# Sheet_Gloves.net
KiCad netlist of a schematic drawn in Altium Designer
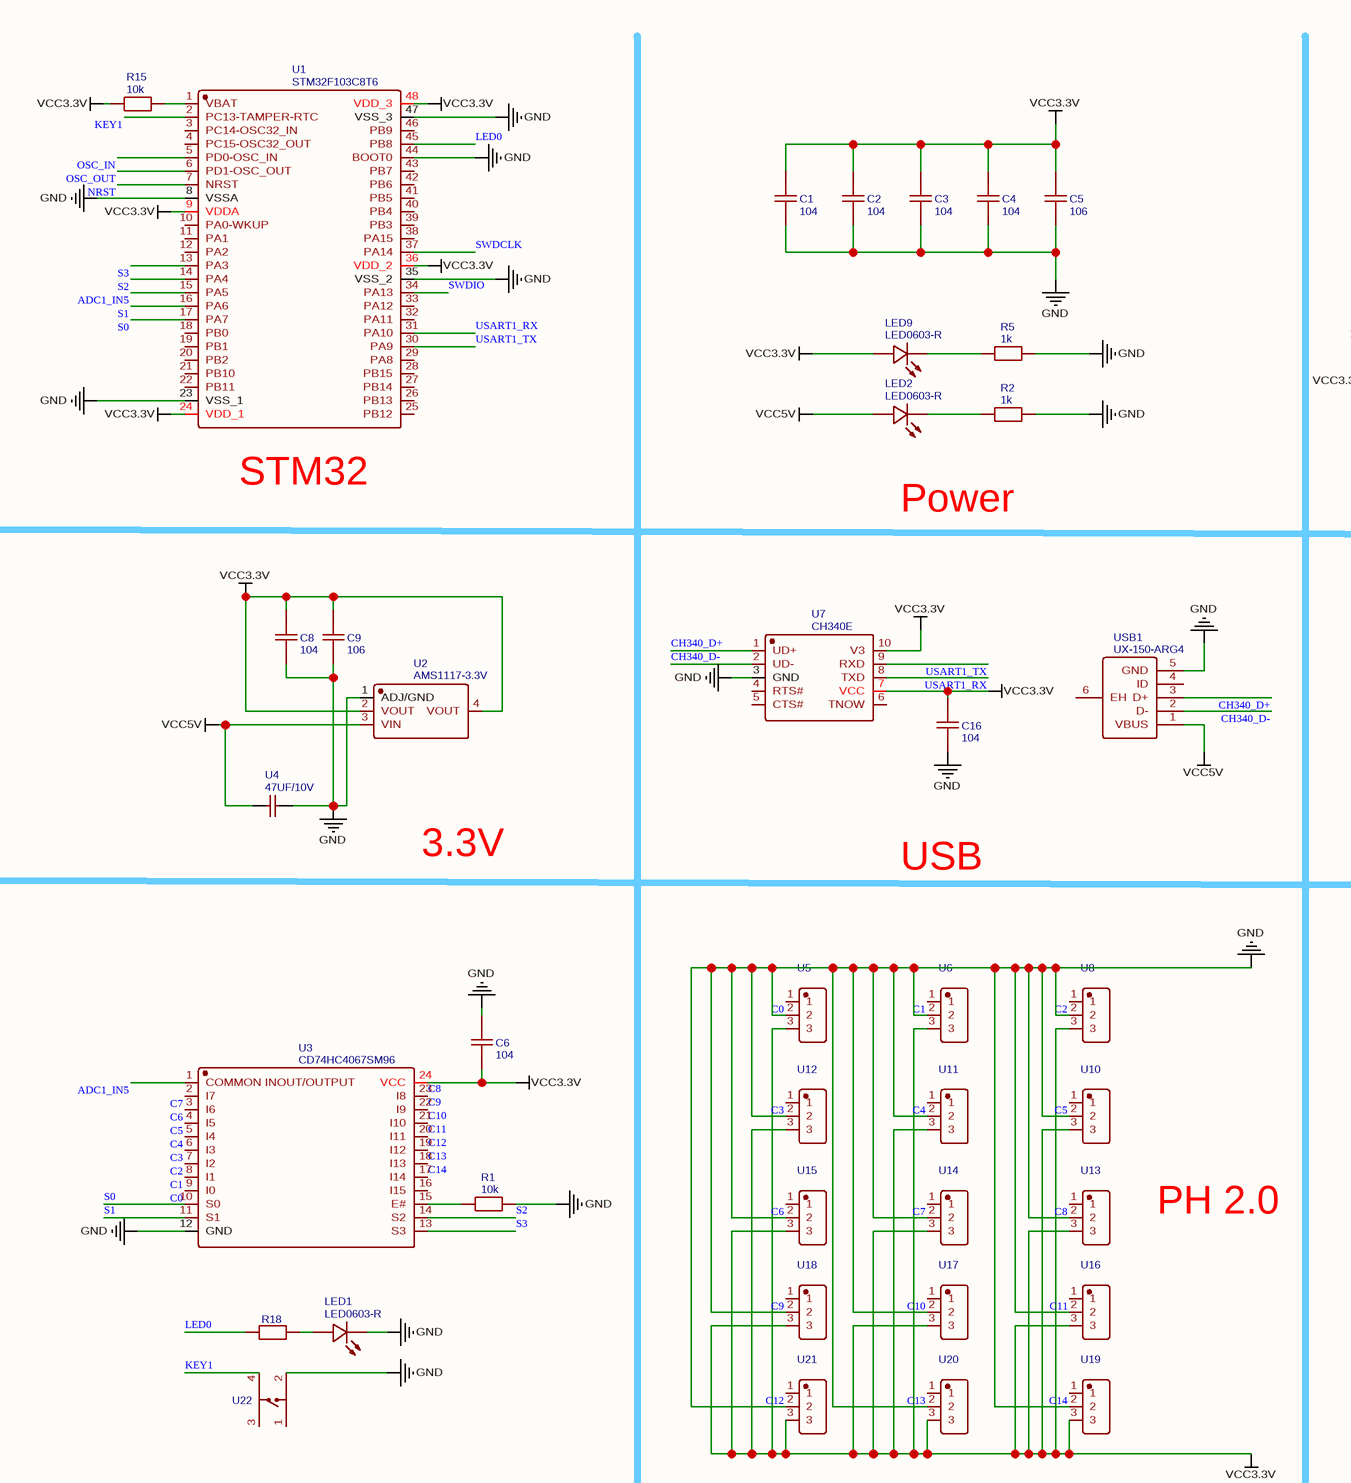
[diagram p0: Sheet_Gloves.schdoc, top left]
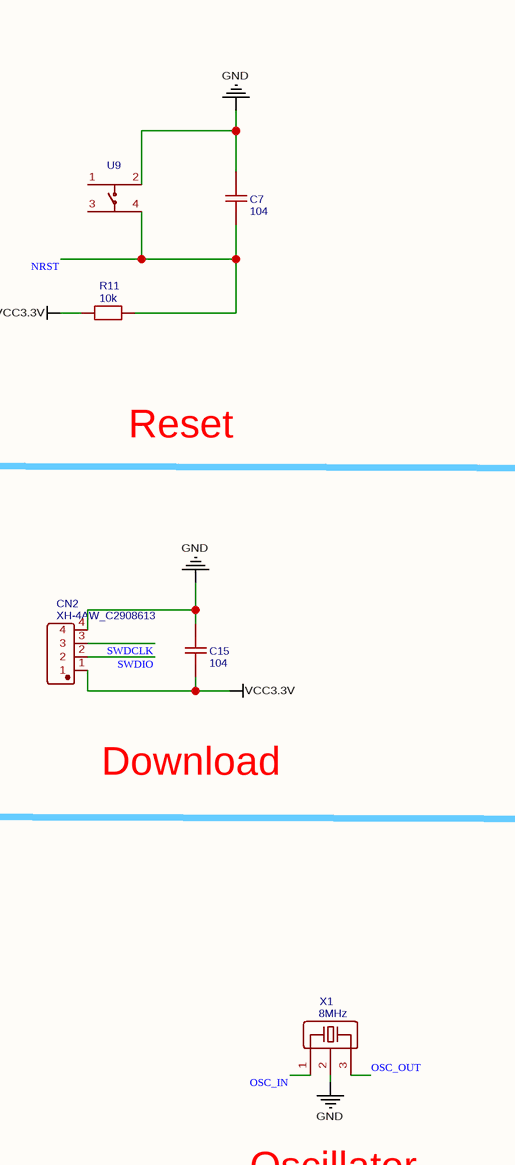
[diagram p1: Sheet_Gloves.schdoc, top right]
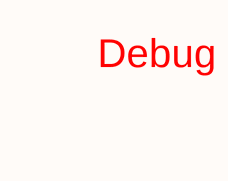
[diagram p2: Sheet_Gloves.schdoc, bottom left]
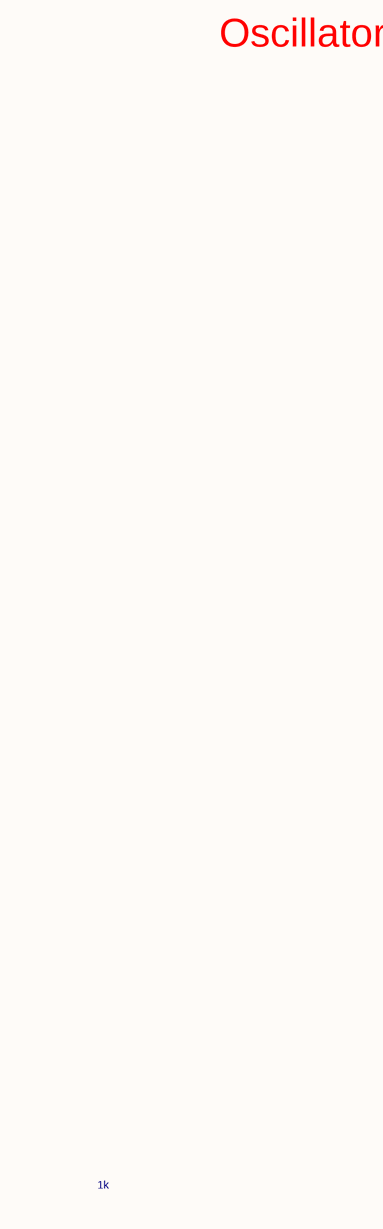
[diagram p3: Sheet_Gloves.schdoc, bottom right]

(export (version "E")
  (design (tool "Eeschema 10.0.6"))
  (components
    (comp (ref "C1")
      (value "104")
      (fields (field (name "CONTRIBUTOR") "LCEDA_Lib"))
      (libsource (lib "altium-import") (part "root_1_104_"))
    )
    (comp (ref "C2")
      (value "104")
      (fields (field (name "CONTRIBUTOR") "LCEDA_Lib"))
      (libsource (lib "altium-import") (part "root_1_104_"))
    )
    (comp (ref "C3")
      (value "104")
      (fields (field (name "CONTRIBUTOR") "LCEDA_Lib"))
      (libsource (lib "altium-import") (part "root_1_104_"))
    )
    (comp (ref "C4")
      (value "104")
      (fields (field (name "CONTRIBUTOR") "LCEDA_Lib"))
      (libsource (lib "altium-import") (part "root_1_104_"))
    )
    (comp (ref "C5")
      (value "106")
      (fields (field (name "CONTRIBUTOR") "LCEDA_Lib"))
      (libsource (lib "altium-import") (part "root_1_106_"))
    )
    (comp (ref "C6")
      (value "104")
      (fields (field (name "CONTRIBUTOR") "LCEDA_Lib"))
      (libsource (lib "altium-import") (part "root_1_104_"))
    )
    (comp (ref "C7")
      (value "104")
      (fields (field (name "CONTRIBUTOR") "LCEDA_Lib"))
      (libsource (lib "altium-import") (part "root_1_104_"))
    )
    (comp (ref "C8")
      (value "104")
      (fields (field (name "CONTRIBUTOR") "LCEDA_Lib"))
      (libsource (lib "altium-import") (part "root_1_104_"))
    )
    (comp (ref "C9")
      (value "106")
      (fields (field (name "CONTRIBUTOR") "LCEDA_Lib"))
      (libsource (lib "altium-import") (part "root_1_106_"))
    )
    (comp (ref "C15")
      (value "104")
      (fields (field (name "CONTRIBUTOR") "LCEDA_Lib"))
      (libsource (lib "altium-import") (part "root_1_104_"))
    )
    (comp (ref "C16")
      (value "104")
      (fields (field (name "CONTRIBUTOR") "LCEDA_Lib"))
      (libsource (lib "altium-import") (part "root_1_104_"))
    )
    (comp (ref "CN2")
      (value "XH-4AW_C2908613")
      (fields
        (field (name "MANUFACTURER") "HCTL(华灿天禄)")
        (field (name "MANUFACTURER PART") "XH-4AW")
        (field (name "CONTRIBUTOR") "LCSC")
      )
      (libsource (lib "altium-import") (part "root_2_XH-4AW_C2908613_"))
    )
    (comp (ref "LED1")
      (value "LED0603-R")
      (fields (field (name "CONTRIBUTOR") "LCSC"))
      (libsource (lib "altium-import") (part "root_2_LED0603-R_"))
    )
    (comp (ref "LED2")
      (value "LED0603-R")
      (fields (field (name "CONTRIBUTOR") "LCSC"))
      (libsource (lib "altium-import") (part "root_2_LED0603-R_"))
    )
    (comp (ref "LED9")
      (value "LED0603-R")
      (fields (field (name "CONTRIBUTOR") "LCSC"))
      (libsource (lib "altium-import") (part "root_2_LED0603-R_"))
    )
    (comp (ref "R1")
      (value "10k")
      (fields (field (name "CONTRIBUTOR") "LCEDA_Lib"))
      (libsource (lib "altium-import") (part "root_0_10k_"))
    )
    (comp (ref "R2")
      (value "1k")
      (fields (field (name "CONTRIBUTOR") "LCEDA_Lib"))
      (libsource (lib "altium-import") (part "root_0_1k_"))
    )
    (comp (ref "R5")
      (value "1k")
      (fields (field (name "CONTRIBUTOR") "LCEDA_Lib"))
      (libsource (lib "altium-import") (part "root_0_1k_"))
    )
    (comp (ref "R11")
      (value "10k")
      (fields (field (name "CONTRIBUTOR") "LCEDA_Lib"))
      (libsource (lib "altium-import") (part "root_0_10k_"))
    )
    (comp (ref "R15")
      (value "10k")
      (fields (field (name "CONTRIBUTOR") "LCEDA_Lib"))
      (libsource (lib "altium-import") (part "root_2_10k_"))
    )
    (comp (ref "R18")
      (value "1k")
      (fields (field (name "CONTRIBUTOR") "LCEDA_Lib"))
      (libsource (lib "altium-import") (part "root_0_1k_"))
    )
    (comp (ref "U1")
      (value "STM32F103C8T6")
      (fields (field (name "MANUFACTURER") "ST(意法半导体)"))
      (libsource (lib "altium-import") (part "root_0_STM32F103C8T6_"))
    )
    (comp (ref "U2")
      (value "AMS1117-3.3V")
      (fields (field (name "MANUFACTURER") "WPMtek(维攀微)") (field (name "CONTRIBUTOR") "LCSC"))
      (libsource (lib "altium-import") (part "root_0_AMS1117-3.3V_"))
    )
    (comp (ref "U3")
      (value "CD74HC4067SM96")
      (fields (field (name "MANUFACTURER") "TI(德州仪器)"))
      (libsource (lib "altium-import") (part "root_0_CD74HC4067SM96_"))
    )
    (comp (ref "U4")
      (value "47UF/10V")
      (fields (field (name "MANUFACTURER PART") "47uF/10V") (field (name "CONTRIBUTOR") "LCSC"))
      (libsource (lib "altium-import") (part "root_0_47UF/10V_"))
    )
    (comp (ref "U5")
      (value "WAFER-PH2.0-3PZZ-R62")
      (fields (field (name "MANUFACTURER") "XUNPU(讯普)") (field (name "CONTRIBUTOR") "lcsc"))
      (libsource (lib "altium-import") (part "root_0_WAFER-PH2.0-3PZZ-R62_"))
    )
    (comp (ref "U6")
      (value "WAFER-PH2.0-3PZZ-R62")
      (fields (field (name "MANUFACTURER") "XUNPU(讯普)") (field (name "CONTRIBUTOR") "lcsc"))
      (libsource (lib "altium-import") (part "root_0_WAFER-PH2.0-3PZZ-R62_"))
    )
    (comp (ref "U7")
      (value "CH340E")
      (fields (field (name "MANUFACTURER") "WCH(南京沁恒)"))
      (libsource (lib "altium-import") (part "root_0_CH340E_"))
    )
    (comp (ref "U8")
      (value "WAFER-PH2.0-3PZZ-R62")
      (fields (field (name "MANUFACTURER") "XUNPU(讯普)") (field (name "CONTRIBUTOR") "lcsc"))
      (libsource (lib "altium-import") (part "root_0_WAFER-PH2.0-3PZZ-R62_"))
    )
    (comp (ref "U9")
      (value "TPS645-5NC60")
      (fields (field (name "MANUFACTURER") "ROCPU Switches(台普)") (field (name "CONTRIBUTOR") "lcsc"))
      (libsource (lib "altium-import") (part "root_0_TPS645-5NC60_"))
    )
    (comp (ref "U10")
      (value "WAFER-PH2.0-3PZZ-R62")
      (fields (field (name "MANUFACTURER") "XUNPU(讯普)") (field (name "CONTRIBUTOR") "lcsc"))
      (libsource (lib "altium-import") (part "root_0_WAFER-PH2.0-3PZZ-R62_"))
    )
    (comp (ref "U11")
      (value "WAFER-PH2.0-3PZZ-R62")
      (fields (field (name "MANUFACTURER") "XUNPU(讯普)") (field (name "CONTRIBUTOR") "lcsc"))
      (libsource (lib "altium-import") (part "root_0_WAFER-PH2.0-3PZZ-R62_"))
    )
    (comp (ref "U12")
      (value "WAFER-PH2.0-3PZZ-R62")
      (fields (field (name "MANUFACTURER") "XUNPU(讯普)") (field (name "CONTRIBUTOR") "lcsc"))
      (libsource (lib "altium-import") (part "root_0_WAFER-PH2.0-3PZZ-R62_"))
    )
    (comp (ref "U13")
      (value "WAFER-PH2.0-3PZZ-R62")
      (fields (field (name "MANUFACTURER") "XUNPU(讯普)") (field (name "CONTRIBUTOR") "lcsc"))
      (libsource (lib "altium-import") (part "root_0_WAFER-PH2.0-3PZZ-R62_"))
    )
    (comp (ref "U14")
      (value "WAFER-PH2.0-3PZZ-R62")
      (fields (field (name "MANUFACTURER") "XUNPU(讯普)") (field (name "CONTRIBUTOR") "lcsc"))
      (libsource (lib "altium-import") (part "root_0_WAFER-PH2.0-3PZZ-R62_"))
    )
    (comp (ref "U15")
      (value "WAFER-PH2.0-3PZZ-R62")
      (fields (field (name "MANUFACTURER") "XUNPU(讯普)") (field (name "CONTRIBUTOR") "lcsc"))
      (libsource (lib "altium-import") (part "root_0_WAFER-PH2.0-3PZZ-R62_"))
    )
    (comp (ref "U16")
      (value "WAFER-PH2.0-3PZZ-R62")
      (fields (field (name "MANUFACTURER") "XUNPU(讯普)") (field (name "CONTRIBUTOR") "lcsc"))
      (libsource (lib "altium-import") (part "root_0_WAFER-PH2.0-3PZZ-R62_"))
    )
    (comp (ref "U17")
      (value "WAFER-PH2.0-3PZZ-R62")
      (fields (field (name "MANUFACTURER") "XUNPU(讯普)") (field (name "CONTRIBUTOR") "lcsc"))
      (libsource (lib "altium-import") (part "root_0_WAFER-PH2.0-3PZZ-R62_"))
    )
    (comp (ref "U18")
      (value "WAFER-PH2.0-3PZZ-R62")
      (fields (field (name "MANUFACTURER") "XUNPU(讯普)") (field (name "CONTRIBUTOR") "lcsc"))
      (libsource (lib "altium-import") (part "root_0_WAFER-PH2.0-3PZZ-R62_"))
    )
    (comp (ref "U19")
      (value "WAFER-PH2.0-3PZZ-R62")
      (fields (field (name "MANUFACTURER") "XUNPU(讯普)") (field (name "CONTRIBUTOR") "lcsc"))
      (libsource (lib "altium-import") (part "root_0_WAFER-PH2.0-3PZZ-R62_"))
    )
    (comp (ref "U20")
      (value "WAFER-PH2.0-3PZZ-R62")
      (fields (field (name "MANUFACTURER") "XUNPU(讯普)") (field (name "CONTRIBUTOR") "lcsc"))
      (libsource (lib "altium-import") (part "root_0_WAFER-PH2.0-3PZZ-R62_"))
    )
    (comp (ref "U21")
      (value "WAFER-PH2.0-3PZZ-R62")
      (fields (field (name "MANUFACTURER") "XUNPU(讯普)") (field (name "CONTRIBUTOR") "lcsc"))
      (libsource (lib "altium-import") (part "root_0_WAFER-PH2.0-3PZZ-R62_"))
    )
    (comp (ref "U22")
      (value "TPS645-5NC60")
      (fields (field (name "MANUFACTURER") "ROCPU Switches(台普)") (field (name "CONTRIBUTOR") "lcsc"))
      (libsource (lib "altium-import") (part "root_1_TPS645-5NC60_"))
    )
    (comp (ref "USB1")
      (value "UX-150-ARG4")
      (fields (field (name "MANUFACTURER") "XUNPU(讯普)") (field (name "CONTRIBUTOR") "LCSC"))
      (libsource (lib "altium-import") (part "root_2_UX-150-ARG4_"))
    )
    (comp (ref "X1")
      (value "8MHz")
      (fields (field (name "MANUFACTURER PART") "CSTCE8M00G52-R0") (field (name "MANUFACTURER") "muRata(村田)"))
      (libsource (lib "altium-import") (part "root_0_8MHz_"))
    )
  )
  (nets
    (net (code "1") (name "/ADC1_IN5") (class "Default")
      (node (ref "U1") (pin "15") (pinfunction "PA5_15") (pintype "passive"))
      (node (ref "U3") (pin "1") (pinfunction "COMMON_INOUT/OUTPUT_1") (pintype "passive"))
    )
    (net (code "2") (name "/C0") (class "Default")
      (node (ref "U3") (pin "9") (pinfunction "I0_9") (pintype "passive"))
      (node (ref "U5") (pin "1") (pinfunction "1_1") (pintype "passive"))
    )
    (net (code "3") (name "/C1") (class "Default")
      (node (ref "U3") (pin "8") (pinfunction "I1_8") (pintype "passive"))
      (node (ref "U6") (pin "1") (pinfunction "1_1") (pintype "passive"))
    )
    (net (code "4") (name "/C2") (class "Default")
      (node (ref "U3") (pin "7") (pinfunction "I2_7") (pintype "passive"))
      (node (ref "U8") (pin "1") (pinfunction "1_1") (pintype "passive"))
    )
    (net (code "5") (name "/C3") (class "Default")
      (node (ref "U12") (pin "1") (pinfunction "1_1") (pintype "passive"))
      (node (ref "U3") (pin "6") (pinfunction "I3_6") (pintype "passive"))
    )
    (net (code "6") (name "/C4") (class "Default")
      (node (ref "U11") (pin "1") (pinfunction "1_1") (pintype "passive"))
      (node (ref "U3") (pin "5") (pinfunction "I4_5") (pintype "passive"))
    )
    (net (code "7") (name "/C5") (class "Default")
      (node (ref "U10") (pin "1") (pinfunction "1_1") (pintype "passive"))
      (node (ref "U3") (pin "4") (pinfunction "I5_4") (pintype "passive"))
    )
    (net (code "8") (name "/C6") (class "Default")
      (node (ref "U15") (pin "1") (pinfunction "1_1") (pintype "passive"))
      (node (ref "U3") (pin "3") (pinfunction "I6_3") (pintype "passive"))
    )
    (net (code "9") (name "/C7") (class "Default")
      (node (ref "U14") (pin "1") (pinfunction "1_1") (pintype "passive"))
      (node (ref "U3") (pin "2") (pinfunction "I7_2") (pintype "passive"))
    )
    (net (code "10") (name "/C8") (class "Default")
      (node (ref "U13") (pin "1") (pinfunction "1_1") (pintype "passive"))
      (node (ref "U3") (pin "23") (pinfunction "I8_23") (pintype "passive"))
    )
    (net (code "11") (name "/C9") (class "Default")
      (node (ref "U18") (pin "1") (pinfunction "1_1") (pintype "passive"))
      (node (ref "U3") (pin "22") (pinfunction "I9_22") (pintype "passive"))
    )
    (net (code "12") (name "/C10") (class "Default")
      (node (ref "U17") (pin "1") (pinfunction "1_1") (pintype "passive"))
      (node (ref "U3") (pin "21") (pinfunction "I10_21") (pintype "passive"))
    )
    (net (code "13") (name "/C11") (class "Default")
      (node (ref "U16") (pin "1") (pinfunction "1_1") (pintype "passive"))
      (node (ref "U3") (pin "20") (pinfunction "I11_20") (pintype "passive"))
    )
    (net (code "14") (name "/C12") (class "Default")
      (node (ref "U21") (pin "1") (pinfunction "1_1") (pintype "passive"))
      (node (ref "U3") (pin "19") (pinfunction "I12_19") (pintype "passive"))
    )
    (net (code "15") (name "/C13") (class "Default")
      (node (ref "U20") (pin "1") (pinfunction "1_1") (pintype "passive"))
      (node (ref "U3") (pin "18") (pinfunction "I13_18") (pintype "passive"))
    )
    (net (code "16") (name "/C14") (class "Default")
      (node (ref "U19") (pin "1") (pinfunction "1_1") (pintype "passive"))
      (node (ref "U3") (pin "17") (pinfunction "I14_17") (pintype "passive"))
    )
    (net (code "17") (name "/CH340_D+") (class "Default")
      (node (ref "U7") (pin "1") (pinfunction "UD+_1") (pintype "passive"))
      (node (ref "USB1") (pin "3") (pinfunction "D+_3") (pintype "passive"))
    )
    (net (code "18") (name "/CH340_D-") (class "Default")
      (node (ref "U7") (pin "2") (pinfunction "UD-_2") (pintype "passive"))
      (node (ref "USB1") (pin "2") (pinfunction "D-_2") (pintype "passive"))
    )
    (net (code "19") (name "/KEY1") (class "Default")
      (node (ref "U1") (pin "2") (pinfunction "PC13-TAMPER-RTC_2") (pintype "passive"))
      (node (ref "U22") (pin "4") (pinfunction "4_4") (pintype "passive"))
    )
    (net (code "20") (name "/LED0") (class "Default")
      (node (ref "R18") (pin "1") (pinfunction "1_1") (pintype "passive"))
      (node (ref "U1") (pin "45") (pinfunction "PB8_45") (pintype "passive"))
    )
    (net (code "21") (name "/NRST") (class "Default")
      (node (ref "C7") (pin "1") (pinfunction "1_1") (pintype "passive"))
      (node (ref "R11") (pin "2") (pinfunction "2_2") (pintype "passive"))
      (node (ref "U1") (pin "7") (pinfunction "NRST_7") (pintype "passive"))
      (node (ref "U9") (pin "4") (pinfunction "4_4") (pintype "passive"))
    )
    (net (code "22") (name "/OSC_IN") (class "Default")
      (node (ref "U1") (pin "5") (pinfunction "PD0-OSC_IN_5") (pintype "passive"))
      (node (ref "X1") (pin "1") (pinfunction "1_1") (pintype "passive"))
    )
    (net (code "23") (name "/OSC_OUT") (class "Default")
      (node (ref "U1") (pin "6") (pinfunction "PD1-OSC_OUT_6") (pintype "passive"))
      (node (ref "X1") (pin "3") (pinfunction "3_3") (pintype "passive"))
    )
    (net (code "24") (name "/S0") (class "Default")
      (node (ref "U1") (pin "17") (pinfunction "PA7_17") (pintype "passive"))
      (node (ref "U3") (pin "10") (pinfunction "S0_10") (pintype "passive"))
    )
    (net (code "25") (name "/S1") (class "Default")
      (node (ref "U1") (pin "16") (pinfunction "PA6_16") (pintype "passive"))
      (node (ref "U3") (pin "11") (pinfunction "S1_11") (pintype "passive"))
    )
    (net (code "26") (name "/S2") (class "Default")
      (node (ref "U1") (pin "14") (pinfunction "PA4_14") (pintype "passive"))
      (node (ref "U3") (pin "14") (pinfunction "S2_14") (pintype "passive"))
    )
    (net (code "27") (name "/S3") (class "Default")
      (node (ref "U1") (pin "13") (pinfunction "PA3_13") (pintype "passive"))
      (node (ref "U3") (pin "13") (pinfunction "S3_13") (pintype "passive"))
    )
    (net (code "28") (name "/SWDCLK") (class "Default")
      (node (ref "CN2") (pin "3") (pinfunction "3_3") (pintype "passive"))
      (node (ref "U1") (pin "37") (pinfunction "PA14_37") (pintype "passive"))
    )
    (net (code "29") (name "/SWDIO") (class "Default")
      (node (ref "CN2") (pin "2") (pinfunction "2_2") (pintype "passive"))
      (node (ref "U1") (pin "34") (pinfunction "PA13_34") (pintype "passive"))
    )
    (net (code "30") (name "/USART1_RX") (class "Default")
      (node (ref "U1") (pin "31") (pinfunction "PA10_31") (pintype "passive"))
      (node (ref "U7") (pin "8") (pinfunction "TXD_8") (pintype "passive"))
    )
    (net (code "31") (name "/USART1_TX") (class "Default")
      (node (ref "U1") (pin "30") (pinfunction "PA9_30") (pintype "passive"))
      (node (ref "U7") (pin "9") (pinfunction "RXD_9") (pintype "passive"))
    )
    (net (code "32") (name "GND") (class "Default")
      (node (ref "C1") (pin "1") (pinfunction "1_1") (pintype "passive"))
      (node (ref "C15") (pin "2") (pinfunction "2_2") (pintype "passive"))
      (node (ref "C16") (pin "1") (pinfunction "1_1") (pintype "passive"))
      (node (ref "C2") (pin "1") (pinfunction "1_1") (pintype "passive"))
      (node (ref "C3") (pin "1") (pinfunction "1_1") (pintype "passive"))
      (node (ref "C4") (pin "1") (pinfunction "1_1") (pintype "passive"))
      (node (ref "C5") (pin "1") (pinfunction "1_1") (pintype "passive"))
      (node (ref "C6") (pin "2") (pinfunction "2_2") (pintype "passive"))
      (node (ref "C7") (pin "2") (pinfunction "2_2") (pintype "passive"))
      (node (ref "C8") (pin "1") (pinfunction "1_1") (pintype "passive"))
      (node (ref "C9") (pin "1") (pinfunction "1_1") (pintype "passive"))
      (node (ref "CN2") (pin "4") (pinfunction "4_4") (pintype "passive"))
      (node (ref "LED1") (pin "2") (pinfunction "K_2") (pintype "passive"))
      (node (ref "R1") (pin "2") (pinfunction "2_2") (pintype "passive"))
      (node (ref "R2") (pin "2") (pinfunction "2_2") (pintype "passive"))
      (node (ref "R5") (pin "2") (pinfunction "2_2") (pintype "passive"))
      (node (ref "U1") (pin "23") (pinfunction "VSS_1_23") (pintype "passive"))
      (node (ref "U1") (pin "35") (pinfunction "VSS_2_35") (pintype "passive"))
      (node (ref "U1") (pin "44") (pinfunction "BOOT0_44") (pintype "passive"))
      (node (ref "U1") (pin "47") (pinfunction "VSS_3_47") (pintype "passive"))
      (node (ref "U1") (pin "8") (pinfunction "VSSA_8") (pintype "passive"))
      (node (ref "U10") (pin "2") (pinfunction "2_2") (pintype "passive"))
      (node (ref "U11") (pin "2") (pinfunction "2_2") (pintype "passive"))
      (node (ref "U12") (pin "2") (pinfunction "2_2") (pintype "passive"))
      (node (ref "U13") (pin "2") (pinfunction "2_2") (pintype "passive"))
      (node (ref "U14") (pin "2") (pinfunction "2_2") (pintype "passive"))
      (node (ref "U15") (pin "2") (pinfunction "2_2") (pintype "passive"))
      (node (ref "U16") (pin "2") (pinfunction "2_2") (pintype "passive"))
      (node (ref "U17") (pin "2") (pinfunction "2_2") (pintype "passive"))
      (node (ref "U18") (pin "2") (pinfunction "2_2") (pintype "passive"))
      (node (ref "U19") (pin "2") (pinfunction "2_2") (pintype "passive"))
      (node (ref "U2") (pin "1") (pinfunction "ADJ/GND_1") (pintype "passive"))
      (node (ref "U20") (pin "2") (pinfunction "2_2") (pintype "passive"))
      (node (ref "U21") (pin "2") (pinfunction "2_2") (pintype "passive"))
      (node (ref "U22") (pin "2") (pinfunction "2_2") (pintype "passive"))
      (node (ref "U3") (pin "12") (pinfunction "GND_12") (pintype "passive"))
      (node (ref "U4") (pin "2") (pinfunction "2_2") (pintype "passive"))
      (node (ref "U5") (pin "2") (pinfunction "2_2") (pintype "passive"))
      (node (ref "U6") (pin "2") (pinfunction "2_2") (pintype "passive"))
      (node (ref "U7") (pin "3") (pinfunction "GND_3") (pintype "passive"))
      (node (ref "U8") (pin "2") (pinfunction "2_2") (pintype "passive"))
      (node (ref "U9") (pin "2") (pinfunction "2_2") (pintype "passive"))
      (node (ref "USB1") (pin "5") (pinfunction "GND_5") (pintype "passive"))
      (node (ref "X1") (pin "2") (pinfunction "2_2") (pintype "passive"))
    )
    (net (code "33") (name "Net-(LED1-A)") (class "Default")
      (node (ref "LED1") (pin "1") (pinfunction "A_1") (pintype "passive"))
      (node (ref "R18") (pin "2") (pinfunction "2_2") (pintype "passive"))
    )
    (net (code "34") (name "Net-(LED2-K)") (class "Default")
      (node (ref "LED2") (pin "2") (pinfunction "K_2") (pintype "passive"))
      (node (ref "R2") (pin "1") (pinfunction "1_1") (pintype "passive"))
    )
    (net (code "35") (name "Net-(LED9-K)") (class "Default")
      (node (ref "LED9") (pin "2") (pinfunction "K_2") (pintype "passive"))
      (node (ref "R5") (pin "1") (pinfunction "1_1") (pintype "passive"))
    )
    (net (code "36") (name "Net-(U1-VBAT)") (class "Default")
      (node (ref "R15") (pin "1") (pinfunction "1_1") (pintype "passive"))
      (node (ref "U1") (pin "1") (pinfunction "VBAT_1") (pintype "passive"))
    )
    (net (code "37") (name "Net-(U3-E#)") (class "Default")
      (node (ref "R1") (pin "1") (pinfunction "1_1") (pintype "passive"))
      (node (ref "U3") (pin "15") (pinfunction "E#_15") (pintype "passive"))
    )
    (net (code "38") (name "VCC3.3V") (class "Default")
      (node (ref "C1") (pin "2") (pinfunction "2_2") (pintype "passive"))
      (node (ref "C15") (pin "1") (pinfunction "1_1") (pintype "passive"))
      (node (ref "C16") (pin "2") (pinfunction "2_2") (pintype "passive"))
      (node (ref "C2") (pin "2") (pinfunction "2_2") (pintype "passive"))
      (node (ref "C3") (pin "2") (pinfunction "2_2") (pintype "passive"))
      (node (ref "C4") (pin "2") (pinfunction "2_2") (pintype "passive"))
      (node (ref "C5") (pin "2") (pinfunction "2_2") (pintype "passive"))
      (node (ref "C6") (pin "1") (pinfunction "1_1") (pintype "passive"))
      (node (ref "C8") (pin "2") (pinfunction "2_2") (pintype "passive"))
      (node (ref "C9") (pin "2") (pinfunction "2_2") (pintype "passive"))
      (node (ref "CN2") (pin "1") (pinfunction "1_1") (pintype "passive"))
      (node (ref "LED9") (pin "1") (pinfunction "A_1") (pintype "passive"))
      (node (ref "R11") (pin "1") (pinfunction "1_1") (pintype "passive"))
      (node (ref "R15") (pin "2") (pinfunction "2_2") (pintype "passive"))
      (node (ref "U1") (pin "24") (pinfunction "VDD_1_24") (pintype "passive"))
      (node (ref "U1") (pin "36") (pinfunction "VDD_2_36") (pintype "passive"))
      (node (ref "U1") (pin "48") (pinfunction "VDD_3_48") (pintype "passive"))
      (node (ref "U1") (pin "9") (pinfunction "VDDA_9") (pintype "passive"))
      (node (ref "U10") (pin "3") (pinfunction "3_3") (pintype "passive"))
      (node (ref "U11") (pin "3") (pinfunction "3_3") (pintype "passive"))
      (node (ref "U12") (pin "3") (pinfunction "3_3") (pintype "passive"))
      (node (ref "U13") (pin "3") (pinfunction "3_3") (pintype "passive"))
      (node (ref "U14") (pin "3") (pinfunction "3_3") (pintype "passive"))
      (node (ref "U15") (pin "3") (pinfunction "3_3") (pintype "passive"))
      (node (ref "U16") (pin "3") (pinfunction "3_3") (pintype "passive"))
      (node (ref "U17") (pin "3") (pinfunction "3_3") (pintype "passive"))
      (node (ref "U18") (pin "3") (pinfunction "3_3") (pintype "passive"))
      (node (ref "U19") (pin "3") (pinfunction "3_3") (pintype "passive"))
      (node (ref "U2") (pin "2") (pinfunction "VOUT_2") (pintype "passive"))
      (node (ref "U2") (pin "4") (pinfunction "VOUT_4") (pintype "passive"))
      (node (ref "U20") (pin "3") (pinfunction "3_3") (pintype "passive"))
      (node (ref "U21") (pin "3") (pinfunction "3_3") (pintype "passive"))
      (node (ref "U3") (pin "24") (pinfunction "VCC_24") (pintype "passive"))
      (node (ref "U5") (pin "3") (pinfunction "3_3") (pintype "passive"))
      (node (ref "U6") (pin "3") (pinfunction "3_3") (pintype "passive"))
      (node (ref "U7") (pin "10") (pinfunction "V3_10") (pintype "passive"))
      (node (ref "U7") (pin "7") (pinfunction "VCC_7") (pintype "passive"))
      (node (ref "U8") (pin "3") (pinfunction "3_3") (pintype "passive"))
    )
    (net (code "39") (name "VCC5V") (class "Default")
      (node (ref "LED2") (pin "1") (pinfunction "A_1") (pintype "passive"))
      (node (ref "U2") (pin "3") (pinfunction "VIN_3") (pintype "passive"))
      (node (ref "U4") (pin "1") (pinfunction "1_1") (pintype "passive"))
      (node (ref "USB1") (pin "1") (pinfunction "VBUS_1") (pintype "passive"))
    )
    (net (code "40") (name "unconnected-(U1-PA0-WKUP-Pad10)") (class "Default")
      (node (ref "U1") (pin "10") (pinfunction "PA0-WKUP_10") (pintype "passive"))
    )
    (net (code "41") (name "unconnected-(U1-PA1-Pad11)") (class "Default")
      (node (ref "U1") (pin "11") (pinfunction "PA1_11") (pintype "passive"))
    )
    (net (code "42") (name "unconnected-(U1-PA2-Pad12)") (class "Default")
      (node (ref "U1") (pin "12") (pinfunction "PA2_12") (pintype "passive"))
    )
    (net (code "43") (name "unconnected-(U1-PA8-Pad29)") (class "Default")
      (node (ref "U1") (pin "29") (pinfunction "PA8_29") (pintype "passive"))
    )
    (net (code "44") (name "unconnected-(U1-PA11-Pad32)") (class "Default")
      (node (ref "U1") (pin "32") (pinfunction "PA11_32") (pintype "passive"))
    )
    (net (code "45") (name "unconnected-(U1-PA12-Pad33)") (class "Default")
      (node (ref "U1") (pin "33") (pinfunction "PA12_33") (pintype "passive"))
    )
    (net (code "46") (name "unconnected-(U1-PA15-Pad38)") (class "Default")
      (node (ref "U1") (pin "38") (pinfunction "PA15_38") (pintype "passive"))
    )
    (net (code "47") (name "unconnected-(U1-PB0-Pad18)") (class "Default")
      (node (ref "U1") (pin "18") (pinfunction "PB0_18") (pintype "passive"))
    )
    (net (code "48") (name "unconnected-(U1-PB1-Pad19)") (class "Default")
      (node (ref "U1") (pin "19") (pinfunction "PB1_19") (pintype "passive"))
    )
    (net (code "49") (name "unconnected-(U1-PB2-Pad20)") (class "Default")
      (node (ref "U1") (pin "20") (pinfunction "PB2_20") (pintype "passive"))
    )
    (net (code "50") (name "unconnected-(U1-PB3-Pad39)") (class "Default")
      (node (ref "U1") (pin "39") (pinfunction "PB3_39") (pintype "passive"))
    )
    (net (code "51") (name "unconnected-(U1-PB4-Pad40)") (class "Default")
      (node (ref "U1") (pin "40") (pinfunction "PB4_40") (pintype "passive"))
    )
    (net (code "52") (name "unconnected-(U1-PB5-Pad41)") (class "Default")
      (node (ref "U1") (pin "41") (pinfunction "PB5_41") (pintype "passive"))
    )
    (net (code "53") (name "unconnected-(U1-PB6-Pad42)") (class "Default")
      (node (ref "U1") (pin "42") (pinfunction "PB6_42") (pintype "passive"))
    )
    (net (code "54") (name "unconnected-(U1-PB7-Pad43)") (class "Default")
      (node (ref "U1") (pin "43") (pinfunction "PB7_43") (pintype "passive"))
    )
    (net (code "55") (name "unconnected-(U1-PB9-Pad46)") (class "Default")
      (node (ref "U1") (pin "46") (pinfunction "PB9_46") (pintype "passive"))
    )
    (net (code "56") (name "unconnected-(U1-PB10-Pad21)") (class "Default")
      (node (ref "U1") (pin "21") (pinfunction "PB10_21") (pintype "passive"))
    )
    (net (code "57") (name "unconnected-(U1-PB11-Pad22)") (class "Default")
      (node (ref "U1") (pin "22") (pinfunction "PB11_22") (pintype "passive"))
    )
    (net (code "58") (name "unconnected-(U1-PB12-Pad25)") (class "Default")
      (node (ref "U1") (pin "25") (pinfunction "PB12_25") (pintype "passive"))
    )
    (net (code "59") (name "unconnected-(U1-PB13-Pad26)") (class "Default")
      (node (ref "U1") (pin "26") (pinfunction "PB13_26") (pintype "passive"))
    )
    (net (code "60") (name "unconnected-(U1-PB14-Pad27)") (class "Default")
      (node (ref "U1") (pin "27") (pinfunction "PB14_27") (pintype "passive"))
    )
    (net (code "61") (name "unconnected-(U1-PB15-Pad28)") (class "Default")
      (node (ref "U1") (pin "28") (pinfunction "PB15_28") (pintype "passive"))
    )
    (net (code "62") (name "unconnected-(U1-PC14-OSC32_IN-Pad3)") (class "Default")
      (node (ref "U1") (pin "3") (pinfunction "PC14-OSC32_IN_3") (pintype "passive"))
    )
    (net (code "63") (name "unconnected-(U1-PC15-OSC32_OUT-Pad4)") (class "Default")
      (node (ref "U1") (pin "4") (pinfunction "PC15-OSC32_OUT_4") (pintype "passive"))
    )
    (net (code "64") (name "unconnected-(U3-I15-Pad16)") (class "Default")
      (node (ref "U3") (pin "16") (pinfunction "I15_16") (pintype "passive"))
    )
    (net (code "65") (name "unconnected-(U7-CTS#-Pad5)") (class "Default")
      (node (ref "U7") (pin "5") (pinfunction "CTS#_5") (pintype "passive"))
    )
    (net (code "66") (name "unconnected-(U7-RTS#-Pad4)") (class "Default")
      (node (ref "U7") (pin "4") (pinfunction "RTS#_4") (pintype "passive"))
    )
    (net (code "67") (name "unconnected-(U7-TNOW-Pad6)") (class "Default")
      (node (ref "U7") (pin "6") (pinfunction "TNOW_6") (pintype "passive"))
    )
    (net (code "68") (name "unconnected-(U9-Pad1)") (class "Default")
      (node (ref "U9") (pin "1") (pinfunction "1_1") (pintype "passive"))
    )
    (net (code "69") (name "unconnected-(U9-Pad3)") (class "Default")
      (node (ref "U9") (pin "3") (pinfunction "3_3") (pintype "passive"))
    )
    (net (code "70") (name "unconnected-(U22-Pad1)") (class "Default")
      (node (ref "U22") (pin "1") (pinfunction "1_1") (pintype "passive"))
    )
    (net (code "71") (name "unconnected-(U22-Pad3)") (class "Default")
      (node (ref "U22") (pin "3") (pinfunction "3_3") (pintype "passive"))
    )
    (net (code "72") (name "unconnected-(USB1-EH-Pad6)") (class "Default")
      (node (ref "USB1") (pin "6") (pinfunction "EH_6") (pintype "passive"))
    )
    (net (code "73") (name "unconnected-(USB1-ID-Pad4)") (class "Default")
      (node (ref "USB1") (pin "4") (pinfunction "ID_4") (pintype "passive"))
    )
  )
)
